# NVMe__Storage__Ports.net
KiCad netlist of a schematic drawn in Altium Designer
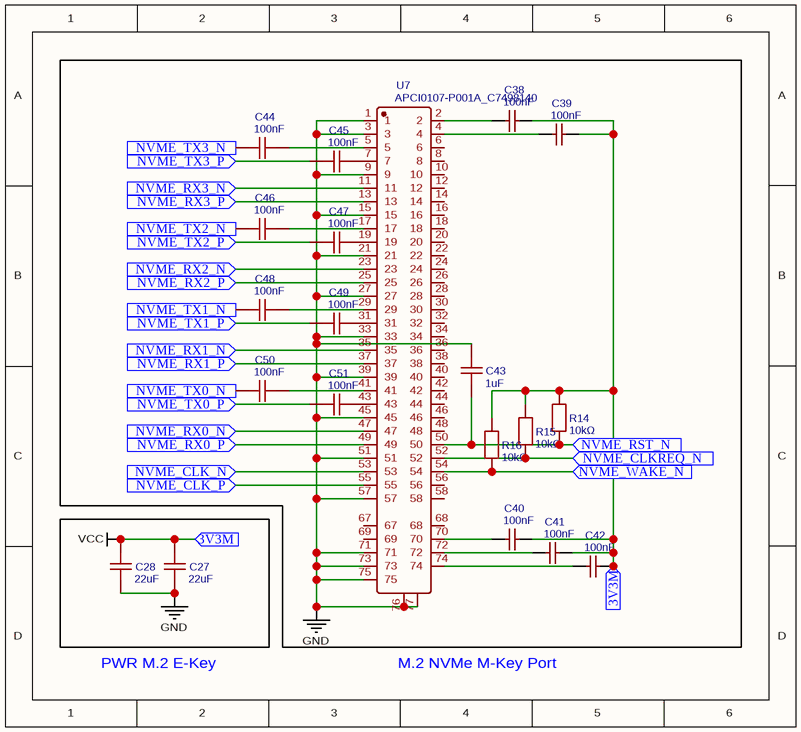
[diagram p0: NVMe_(Storage)_Ports.schdoc]

(export (version "E")
  (design (tool "Eeschema 10.0.6"))
  (components
    (comp (ref "C27")
      (value "22uF")
      (fields
        (field (name "MANUFACTURER") "SAMSUNG(三星)")
        (field (name "MANUFACTURER PART") "CL21A226MAYNNNE")
        (field (name "CONTRIBUTOR") "LCSC")
      )
      (libsource (lib "altium-import") (part "root_1_22uF_"))
    )
    (comp (ref "C28")
      (value "22uF")
      (fields
        (field (name "MANUFACTURER") "SAMSUNG(三星)")
        (field (name "MANUFACTURER PART") "CL21A226MAYNNNE")
        (field (name "CONTRIBUTOR") "LCSC")
      )
      (libsource (lib "altium-import") (part "root_1_22uF_"))
    )
    (comp (ref "C38")
      (value "100nF")
      (fields
        (field (name "MANUFACTURER") "YAGEO(国巨)")
        (field (name "MANUFACTURER PART") "CC0402KRX5R8BB104")
      )
      (libsource (lib "") (part "root_0_100nF__1"))
    )
    (comp (ref "C39")
      (value "100nF")
      (fields
        (field (name "MANUFACTURER") "YAGEO(国巨)")
        (field (name "MANUFACTURER PART") "CC0402KRX5R8BB104")
      )
      (libsource (lib "") (part "root_0_100nF__1"))
    )
    (comp (ref "C40")
      (value "100nF")
      (fields
        (field (name "MANUFACTURER") "YAGEO(国巨)")
        (field (name "MANUFACTURER PART") "CC0402KRX5R8BB104")
      )
      (libsource (lib "") (part "root_0_100nF__1"))
    )
    (comp (ref "C41")
      (value "100nF")
      (fields
        (field (name "MANUFACTURER") "YAGEO(国巨)")
        (field (name "MANUFACTURER PART") "CC0402KRX5R8BB104")
      )
      (libsource (lib "") (part "root_0_100nF__1"))
    )
    (comp (ref "C42")
      (value "100nF")
      (fields
        (field (name "MANUFACTURER") "YAGEO(国巨)")
        (field (name "MANUFACTURER PART") "CC0402KRX5R8BB104")
      )
      (libsource (lib "") (part "root_0_100nF__1"))
    )
    (comp (ref "C43")
      (value "1uF")
      (fields
        (field (name "MANUFACTURER") "Chinocera(华瓷)")
        (field (name "MANUFACTURER PART") "HGC0402R5105K500NTEJ")
        (field (name "CONTRIBUTOR") "lcsc")
      )
      (libsource (lib "altium-import") (part "root_1_1uF_"))
    )
    (comp (ref "C44")
      (value "100nF")
      (fields
        (field (name "MANUFACTURER") "muRata(村田)")
        (field (name "MANUFACTURER PART") "GRM155R71H104KE14J")
        (field (name "CONTRIBUTOR") "lcsc")
      )
      (libsource (lib "altium-import") (part "root_0_100nF_"))
    )
    (comp (ref "C45")
      (value "100nF")
      (fields
        (field (name "MANUFACTURER") "muRata(村田)")
        (field (name "MANUFACTURER PART") "GRM155R71H104KE14J")
        (field (name "CONTRIBUTOR") "lcsc")
      )
      (libsource (lib "altium-import") (part "root_0_100nF_"))
    )
    (comp (ref "C46")
      (value "100nF")
      (fields
        (field (name "MANUFACTURER") "muRata(村田)")
        (field (name "MANUFACTURER PART") "GRM155R71H104KE14J")
        (field (name "CONTRIBUTOR") "lcsc")
      )
      (libsource (lib "altium-import") (part "root_0_100nF_"))
    )
    (comp (ref "C47")
      (value "100nF")
      (fields
        (field (name "MANUFACTURER") "muRata(村田)")
        (field (name "MANUFACTURER PART") "GRM155R71H104KE14J")
        (field (name "CONTRIBUTOR") "lcsc")
      )
      (libsource (lib "altium-import") (part "root_0_100nF_"))
    )
    (comp (ref "C48")
      (value "100nF")
      (fields
        (field (name "MANUFACTURER") "muRata(村田)")
        (field (name "MANUFACTURER PART") "GRM155R71H104KE14J")
        (field (name "CONTRIBUTOR") "lcsc")
      )
      (libsource (lib "altium-import") (part "root_0_100nF_"))
    )
    (comp (ref "C49")
      (value "100nF")
      (fields
        (field (name "MANUFACTURER") "muRata(村田)")
        (field (name "MANUFACTURER PART") "GRM155R71H104KE14J")
        (field (name "CONTRIBUTOR") "lcsc")
      )
      (libsource (lib "altium-import") (part "root_0_100nF_"))
    )
    (comp (ref "C50")
      (value "100nF")
      (fields
        (field (name "MANUFACTURER") "muRata(村田)")
        (field (name "MANUFACTURER PART") "GRM155R71H104KE14J")
        (field (name "CONTRIBUTOR") "lcsc")
      )
      (libsource (lib "altium-import") (part "root_0_100nF_"))
    )
    (comp (ref "C51")
      (value "100nF")
      (fields
        (field (name "MANUFACTURER") "muRata(村田)")
        (field (name "MANUFACTURER PART") "GRM155R71H104KE14J")
        (field (name "CONTRIBUTOR") "lcsc")
      )
      (libsource (lib "altium-import") (part "root_0_100nF_"))
    )
    (comp (ref "R14")
      (value "10kΩ")
      (fields
        (field (name "MANUFACTURER") "FOJAN(富捷)")
        (field (name "MANUFACTURER PART") "FRC0402F1002TS")
        (field (name "CONTRIBUTOR") "LCSC")
      )
      (libsource (lib "altium-import") (part "root_1_10kΩ_"))
    )
    (comp (ref "R15")
      (value "10kΩ")
      (fields
        (field (name "MANUFACTURER") "FOJAN(富捷)")
        (field (name "MANUFACTURER PART") "FRC0402F1002TS")
        (field (name "CONTRIBUTOR") "LCSC")
      )
      (libsource (lib "altium-import") (part "root_1_10kΩ_"))
    )
    (comp (ref "R16")
      (value "10kΩ")
      (fields
        (field (name "MANUFACTURER") "FOJAN(富捷)")
        (field (name "MANUFACTURER PART") "FRC0402F1002TS")
        (field (name "CONTRIBUTOR") "LCSC")
      )
      (libsource (lib "altium-import") (part "root_1_10kΩ_"))
    )
    (comp (ref "U7")
      (value "APCI0107-P001A_C7498140")
      (fields
        (field (name "MANUFACTURER") "LX(连欣科技)")
        (field (name "MANUFACTURER PART") "APCI0107-P001A")
        (field (name "CONTRIBUTOR") "lcsc")
      )
      (libsource (lib "altium-import") (part "root_0_APCI0107-P001A_C7498140_"))
    )
  )
  (nets
    (net (code "1") (name "/NVME_CLKREQ_N") (class "Default")
      (node (ref "R15") (pin "1") (pinfunction "1_1") (pintype "passive"))
      (node (ref "U7") (pin "52") (pinfunction "52_52") (pintype "passive"))
    )
    (net (code "2") (name "/NVME_CLK_N") (class "Default")
      (node (ref "U7") (pin "53") (pinfunction "53_53") (pintype "passive"))
    )
    (net (code "3") (name "/NVME_CLK_P") (class "Default")
      (node (ref "U7") (pin "55") (pinfunction "55_55") (pintype "passive"))
    )
    (net (code "4") (name "/NVME_RST_N") (class "Default")
      (node (ref "C43") (pin "1") (pinfunction "1_1") (pintype "passive"))
      (node (ref "R14") (pin "1") (pinfunction "1_1") (pintype "passive"))
      (node (ref "U7") (pin "50") (pinfunction "50_50") (pintype "passive"))
    )
    (net (code "5") (name "/NVME_RX0_N") (class "Default")
      (node (ref "U7") (pin "47") (pinfunction "47_47") (pintype "passive"))
    )
    (net (code "6") (name "/NVME_RX0_P") (class "Default")
      (node (ref "U7") (pin "49") (pinfunction "49_49") (pintype "passive"))
    )
    (net (code "7") (name "/NVME_RX1_N") (class "Default")
      (node (ref "U7") (pin "35") (pinfunction "35_35") (pintype "passive"))
    )
    (net (code "8") (name "/NVME_RX1_P") (class "Default")
      (node (ref "U7") (pin "37") (pinfunction "37_37") (pintype "passive"))
    )
    (net (code "9") (name "/NVME_RX2_N") (class "Default")
      (node (ref "U7") (pin "23") (pinfunction "23_23") (pintype "passive"))
    )
    (net (code "10") (name "/NVME_RX2_P") (class "Default")
      (node (ref "U7") (pin "25") (pinfunction "25_25") (pintype "passive"))
    )
    (net (code "11") (name "/NVME_RX3_N") (class "Default")
      (node (ref "U7") (pin "11") (pinfunction "11_11") (pintype "passive"))
    )
    (net (code "12") (name "/NVME_RX3_P") (class "Default")
      (node (ref "U7") (pin "13") (pinfunction "13_13") (pintype "passive"))
    )
    (net (code "13") (name "/NVME_TX0_N") (class "Default")
      (node (ref "C50") (pin "1") (pinfunction "1_1") (pintype "passive"))
    )
    (net (code "14") (name "/NVME_TX0_P") (class "Default")
      (node (ref "C51") (pin "1") (pinfunction "1_1") (pintype "passive"))
    )
    (net (code "15") (name "/NVME_TX1_N") (class "Default")
      (node (ref "C48") (pin "1") (pinfunction "1_1") (pintype "passive"))
    )
    (net (code "16") (name "/NVME_TX1_P") (class "Default")
      (node (ref "C49") (pin "1") (pinfunction "1_1") (pintype "passive"))
    )
    (net (code "17") (name "/NVME_TX2_N") (class "Default")
      (node (ref "C46") (pin "1") (pinfunction "1_1") (pintype "passive"))
    )
    (net (code "18") (name "/NVME_TX2_P") (class "Default")
      (node (ref "C47") (pin "1") (pinfunction "1_1") (pintype "passive"))
    )
    (net (code "19") (name "/NVME_TX3_N") (class "Default")
      (node (ref "C44") (pin "1") (pinfunction "1_1") (pintype "passive"))
    )
    (net (code "20") (name "/NVME_TX3_P") (class "Default")
      (node (ref "C45") (pin "1") (pinfunction "1_1") (pintype "passive"))
    )
    (net (code "21") (name "/NVME_WAKE_N") (class "Default")
      (node (ref "R16") (pin "1") (pinfunction "1_1") (pintype "passive"))
      (node (ref "U7") (pin "54") (pinfunction "54_54") (pintype "passive"))
    )
    (net (code "22") (name "GND") (class "Default")
      (node (ref "C27") (pin "1") (pinfunction "1_1") (pintype "passive"))
      (node (ref "C28") (pin "1") (pinfunction "1_1") (pintype "passive"))
      (node (ref "C43") (pin "2") (pinfunction "2_2") (pintype "passive"))
      (node (ref "U7") (pin "1") (pinfunction "1_1") (pintype "passive"))
      (node (ref "U7") (pin "15") (pinfunction "15_15") (pintype "passive"))
      (node (ref "U7") (pin "21") (pinfunction "21_21") (pintype "passive"))
      (node (ref "U7") (pin "27") (pinfunction "27_27") (pintype "passive"))
      (node (ref "U7") (pin "3") (pinfunction "3_3") (pintype "passive"))
      (node (ref "U7") (pin "33") (pinfunction "33_33") (pintype "passive"))
      (node (ref "U7") (pin "39") (pinfunction "39_39") (pintype "passive"))
      (node (ref "U7") (pin "45") (pinfunction "45_45") (pintype "passive"))
      (node (ref "U7") (pin "51") (pinfunction "51_51") (pintype "passive"))
      (node (ref "U7") (pin "57") (pinfunction "57_57") (pintype "passive"))
      (node (ref "U7") (pin "71") (pinfunction "71_71") (pintype "passive"))
      (node (ref "U7") (pin "73") (pinfunction "73_73") (pintype "passive"))
      (node (ref "U7") (pin "75") (pinfunction "75_75") (pintype "passive"))
      (node (ref "U7") (pin "76") (pinfunction "76_76") (pintype "passive"))
      (node (ref "U7") (pin "77") (pinfunction "77_77") (pintype "passive"))
      (node (ref "U7") (pin "9") (pinfunction "9_9") (pintype "passive"))
    )
    (net (code "23") (name "Net-(C38-Pad1)") (class "Default")
      (node (ref "C38") (pin "1") (pinfunction "1_1") (pintype "passive"))
      (node (ref "U7") (pin "2") (pinfunction "2_2") (pintype "passive"))
    )
    (net (code "24") (name "Net-(C39-Pad1)") (class "Default")
      (node (ref "C39") (pin "1") (pinfunction "1_1") (pintype "passive"))
      (node (ref "U7") (pin "4") (pinfunction "4_4") (pintype "passive"))
    )
    (net (code "25") (name "Net-(C40-Pad1)") (class "Default")
      (node (ref "C40") (pin "1") (pinfunction "1_1") (pintype "passive"))
      (node (ref "U7") (pin "70") (pinfunction "70_70") (pintype "passive"))
    )
    (net (code "26") (name "Net-(C41-Pad1)") (class "Default")
      (node (ref "C41") (pin "1") (pinfunction "1_1") (pintype "passive"))
      (node (ref "U7") (pin "72") (pinfunction "72_72") (pintype "passive"))
    )
    (net (code "27") (name "Net-(C42-Pad1)") (class "Default")
      (node (ref "C42") (pin "1") (pinfunction "1_1") (pintype "passive"))
      (node (ref "U7") (pin "74") (pinfunction "74_74") (pintype "passive"))
    )
    (net (code "28") (name "Net-(C44-Pad2)") (class "Default")
      (node (ref "C44") (pin "2") (pinfunction "2_2") (pintype "passive"))
      (node (ref "U7") (pin "5") (pinfunction "5_5") (pintype "passive"))
    )
    (net (code "29") (name "Net-(C45-Pad2)") (class "Default")
      (node (ref "C45") (pin "2") (pinfunction "2_2") (pintype "passive"))
      (node (ref "U7") (pin "7") (pinfunction "7_7") (pintype "passive"))
    )
    (net (code "30") (name "Net-(C46-Pad2)") (class "Default")
      (node (ref "C46") (pin "2") (pinfunction "2_2") (pintype "passive"))
      (node (ref "U7") (pin "17") (pinfunction "17_17") (pintype "passive"))
    )
    (net (code "31") (name "Net-(C47-Pad2)") (class "Default")
      (node (ref "C47") (pin "2") (pinfunction "2_2") (pintype "passive"))
      (node (ref "U7") (pin "19") (pinfunction "19_19") (pintype "passive"))
    )
    (net (code "32") (name "Net-(C48-Pad2)") (class "Default")
      (node (ref "C48") (pin "2") (pinfunction "2_2") (pintype "passive"))
      (node (ref "U7") (pin "29") (pinfunction "29_29") (pintype "passive"))
    )
    (net (code "33") (name "Net-(C49-Pad2)") (class "Default")
      (node (ref "C49") (pin "2") (pinfunction "2_2") (pintype "passive"))
      (node (ref "U7") (pin "31") (pinfunction "31_31") (pintype "passive"))
    )
    (net (code "34") (name "Net-(C50-Pad2)") (class "Default")
      (node (ref "C50") (pin "2") (pinfunction "2_2") (pintype "passive"))
      (node (ref "U7") (pin "41") (pinfunction "41_41") (pintype "passive"))
    )
    (net (code "35") (name "Net-(C51-Pad2)") (class "Default")
      (node (ref "C51") (pin "2") (pinfunction "2_2") (pintype "passive"))
      (node (ref "U7") (pin "43") (pinfunction "43_43") (pintype "passive"))
    )
    (net (code "36") (name "VCC") (class "Default")
      (node (ref "C27") (pin "2") (pinfunction "2_2") (pintype "passive"))
      (node (ref "C28") (pin "2") (pinfunction "2_2") (pintype "passive"))
      (node (ref "C38") (pin "2") (pinfunction "2_2") (pintype "passive"))
      (node (ref "C39") (pin "2") (pinfunction "2_2") (pintype "passive"))
      (node (ref "C40") (pin "2") (pinfunction "2_2") (pintype "passive"))
      (node (ref "C41") (pin "2") (pinfunction "2_2") (pintype "passive"))
      (node (ref "C42") (pin "2") (pinfunction "2_2") (pintype "passive"))
      (node (ref "R14") (pin "2") (pinfunction "2_2") (pintype "passive"))
      (node (ref "R15") (pin "2") (pinfunction "2_2") (pintype "passive"))
      (node (ref "R16") (pin "2") (pinfunction "2_2") (pintype "passive"))
    )
    (net (code "37") (name "unconnected-(U7-Pad6)") (class "Default")
      (node (ref "U7") (pin "6") (pinfunction "6_6") (pintype "passive"))
    )
    (net (code "38") (name "unconnected-(U7-Pad8)") (class "Default")
      (node (ref "U7") (pin "8") (pinfunction "8_8") (pintype "passive"))
    )
    (net (code "39") (name "unconnected-(U7-Pad10)") (class "Default")
      (node (ref "U7") (pin "10") (pinfunction "10_10") (pintype "passive"))
    )
    (net (code "40") (name "unconnected-(U7-Pad12)") (class "Default")
      (node (ref "U7") (pin "12") (pinfunction "12_12") (pintype "passive"))
    )
    (net (code "41") (name "unconnected-(U7-Pad14)") (class "Default")
      (node (ref "U7") (pin "14") (pinfunction "14_14") (pintype "passive"))
    )
    (net (code "42") (name "unconnected-(U7-Pad16)") (class "Default")
      (node (ref "U7") (pin "16") (pinfunction "16_16") (pintype "passive"))
    )
    (net (code "43") (name "unconnected-(U7-Pad18)") (class "Default")
      (node (ref "U7") (pin "18") (pinfunction "18_18") (pintype "passive"))
    )
    (net (code "44") (name "unconnected-(U7-Pad20)") (class "Default")
      (node (ref "U7") (pin "20") (pinfunction "20_20") (pintype "passive"))
    )
    (net (code "45") (name "unconnected-(U7-Pad22)") (class "Default")
      (node (ref "U7") (pin "22") (pinfunction "22_22") (pintype "passive"))
    )
    (net (code "46") (name "unconnected-(U7-Pad24)") (class "Default")
      (node (ref "U7") (pin "24") (pinfunction "24_24") (pintype "passive"))
    )
    (net (code "47") (name "unconnected-(U7-Pad26)") (class "Default")
      (node (ref "U7") (pin "26") (pinfunction "26_26") (pintype "passive"))
    )
    (net (code "48") (name "unconnected-(U7-Pad28)") (class "Default")
      (node (ref "U7") (pin "28") (pinfunction "28_28") (pintype "passive"))
    )
    (net (code "49") (name "unconnected-(U7-Pad30)") (class "Default")
      (node (ref "U7") (pin "30") (pinfunction "30_30") (pintype "passive"))
    )
    (net (code "50") (name "unconnected-(U7-Pad32)") (class "Default")
      (node (ref "U7") (pin "32") (pinfunction "32_32") (pintype "passive"))
    )
    (net (code "51") (name "unconnected-(U7-Pad34)") (class "Default")
      (node (ref "U7") (pin "34") (pinfunction "34_34") (pintype "passive"))
    )
    (net (code "52") (name "unconnected-(U7-Pad36)") (class "Default")
      (node (ref "U7") (pin "36") (pinfunction "36_36") (pintype "passive"))
    )
    (net (code "53") (name "unconnected-(U7-Pad38)") (class "Default")
      (node (ref "U7") (pin "38") (pinfunction "38_38") (pintype "passive"))
    )
    (net (code "54") (name "unconnected-(U7-Pad40)") (class "Default")
      (node (ref "U7") (pin "40") (pinfunction "40_40") (pintype "passive"))
    )
    (net (code "55") (name "unconnected-(U7-Pad42)") (class "Default")
      (node (ref "U7") (pin "42") (pinfunction "42_42") (pintype "passive"))
    )
    (net (code "56") (name "unconnected-(U7-Pad44)") (class "Default")
      (node (ref "U7") (pin "44") (pinfunction "44_44") (pintype "passive"))
    )
    (net (code "57") (name "unconnected-(U7-Pad46)") (class "Default")
      (node (ref "U7") (pin "46") (pinfunction "46_46") (pintype "passive"))
    )
    (net (code "58") (name "unconnected-(U7-Pad48)") (class "Default")
      (node (ref "U7") (pin "48") (pinfunction "48_48") (pintype "passive"))
    )
    (net (code "59") (name "unconnected-(U7-Pad56)") (class "Default")
      (node (ref "U7") (pin "56") (pinfunction "56_56") (pintype "passive"))
    )
    (net (code "60") (name "unconnected-(U7-Pad58)") (class "Default")
      (node (ref "U7") (pin "58") (pinfunction "58_58") (pintype "passive"))
    )
    (net (code "61") (name "unconnected-(U7-Pad67)") (class "Default")
      (node (ref "U7") (pin "67") (pinfunction "67_67") (pintype "passive"))
    )
    (net (code "62") (name "unconnected-(U7-Pad68)") (class "Default")
      (node (ref "U7") (pin "68") (pinfunction "68_68") (pintype "passive"))
    )
    (net (code "63") (name "unconnected-(U7-Pad69)") (class "Default")
      (node (ref "U7") (pin "69") (pinfunction "69_69") (pintype "passive"))
    )
  )
)
